# SOC_POWER_CAPS_SOC_VSS.net
KiCad netlist of a schematic drawn in Altium Designer
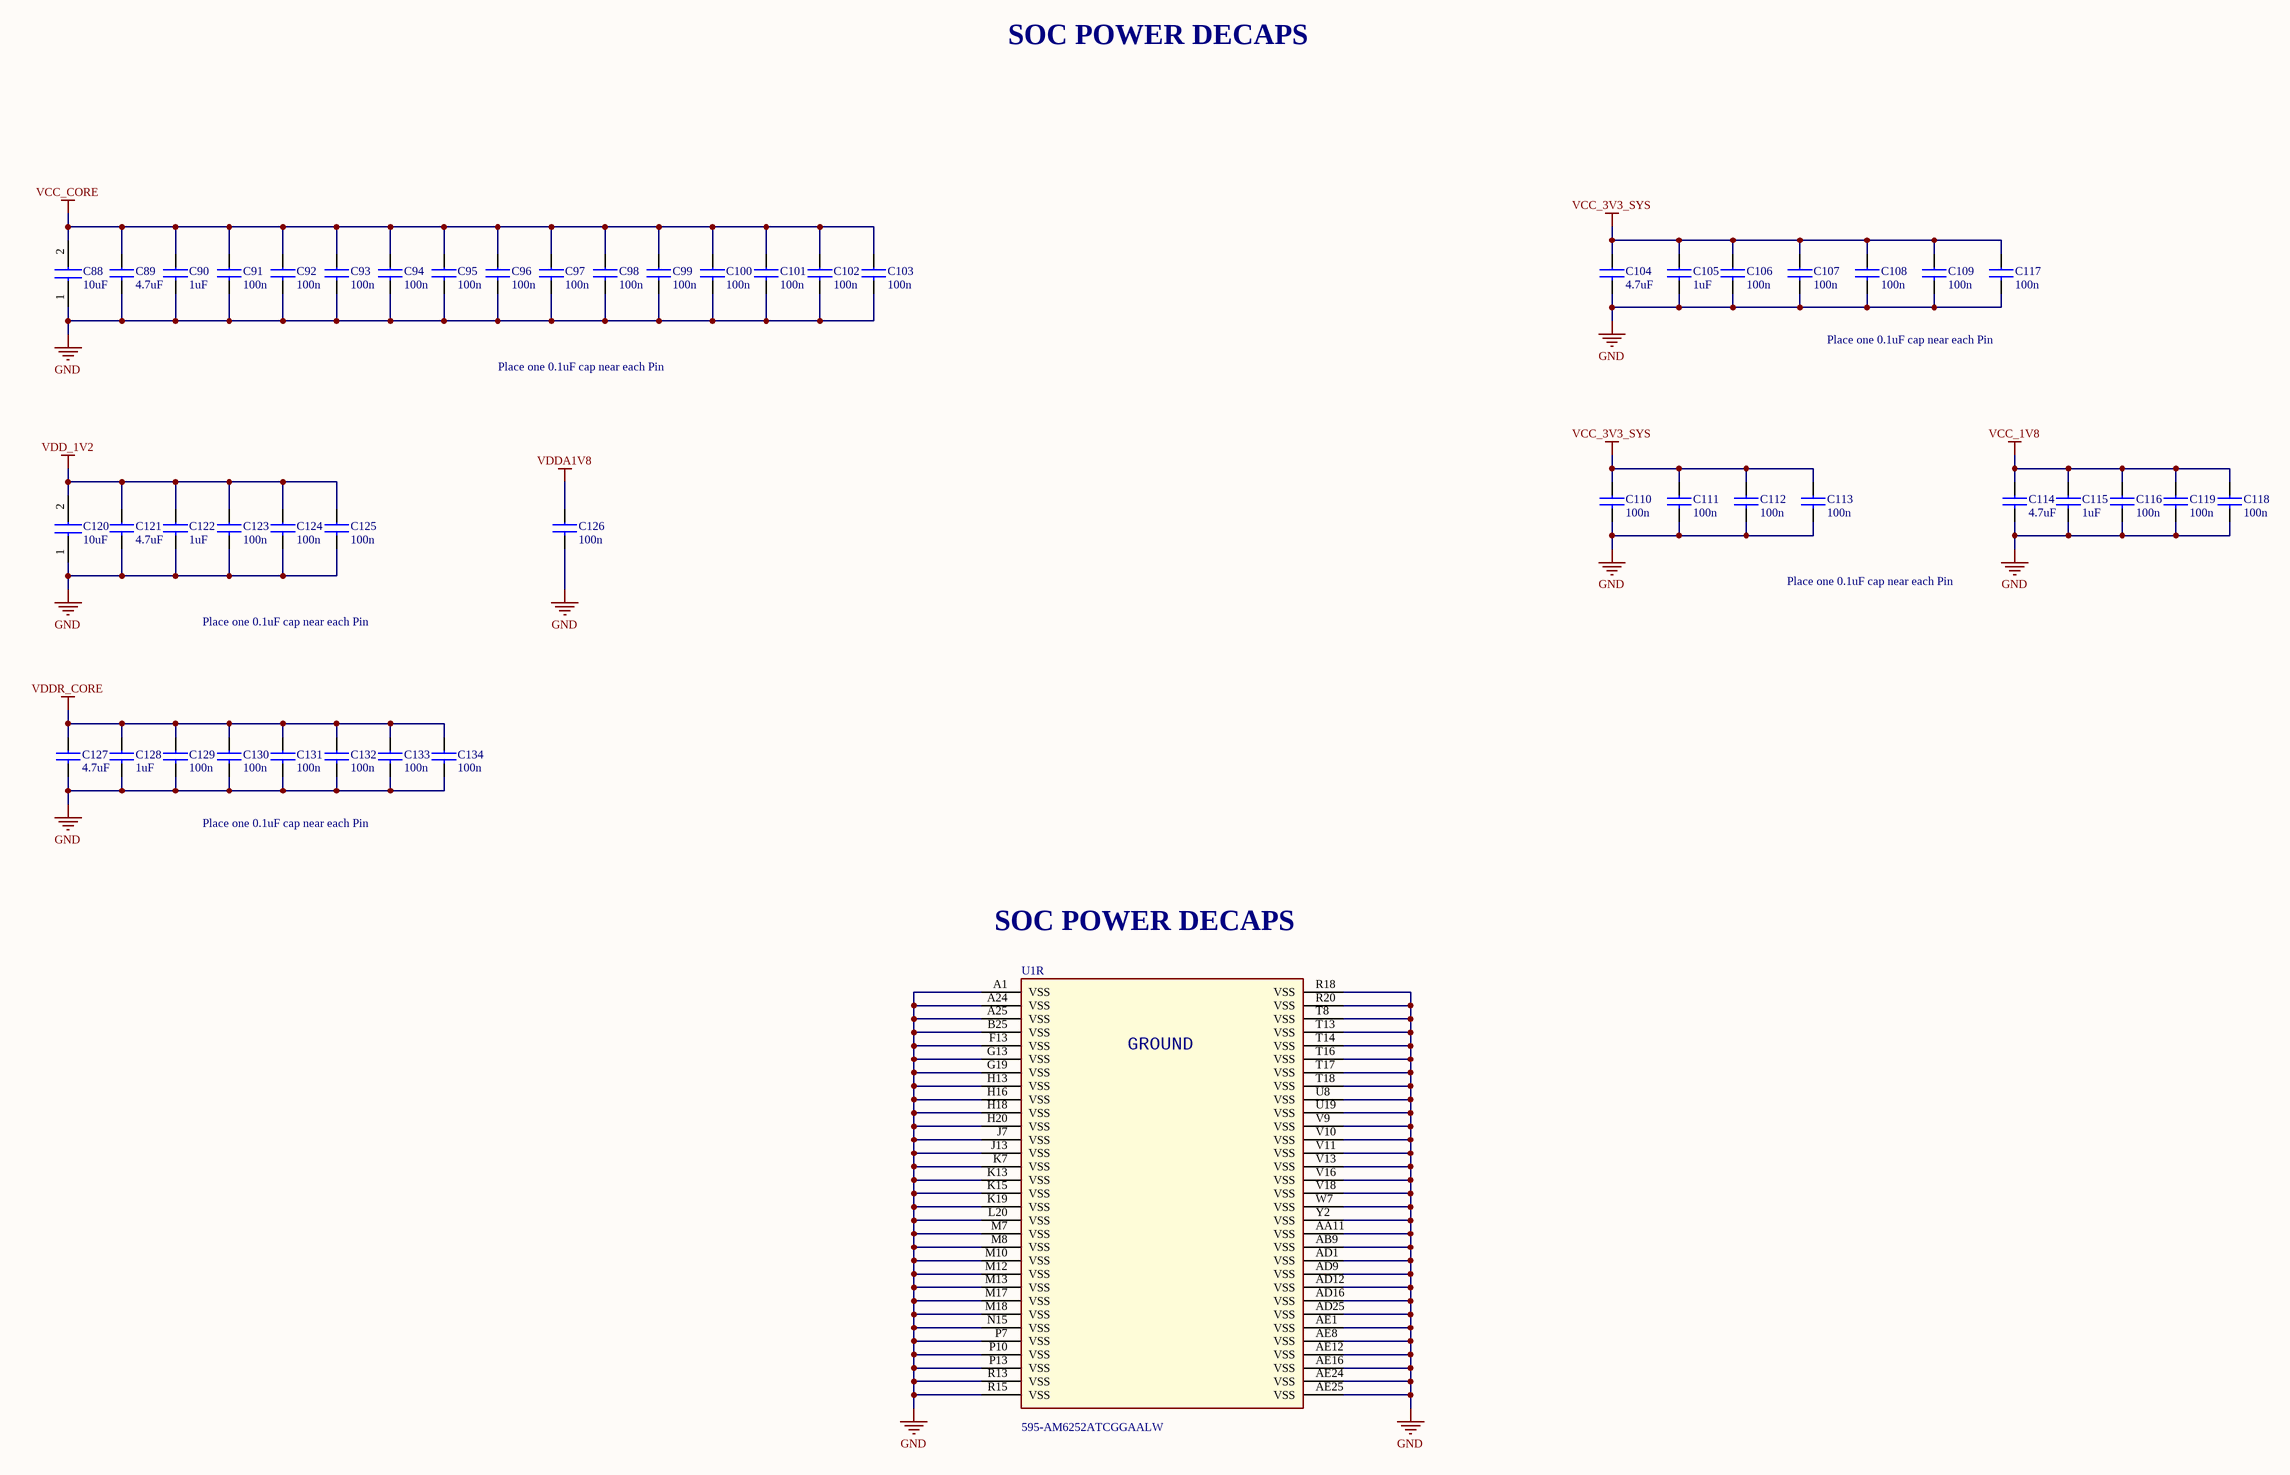
[diagram p0: SOC POWER CAPS & SOC VSS.SchDoc]

(export (version "E")
  (design (tool "Eeschema 10.0.6"))
  (components
    (comp (ref "C88")
      (value "10uF")
      (footprint "C0603")
      (description "10 µF ±20% 6.3V Ceramic Capacitor X5R 0603 (1608 Metric)")
      (fields
        (field (name "MANUFACTURER_PART_NUMBER") "CL10A106MQ8NNNC")
        (field (name "MOUSER PART NUMBER") "187-CL10A106MQ8NNNC")
      )
      (libsource (lib "Schlib AM625") (part "CL10A106MQ8NNNC"))
    )
    (comp (ref "C89")
      (value "4.7uF")
      (footprint "C0201")
      (description "CAP CER 4.7UF 6.3V X5R 0201")
      (fields
        (field (name "MANUFACTURER") "Murata")
        (field (name "MANUFACTURER PART NUMBER") "GRM035R60J475ME15D")
      )
      (libsource (lib "Schlib AM625") (part "GRM035R60J475ME15D"))
    )
    (comp (ref "C90")
      (value "1uF")
      (footprint "C0201")
      (description "CAP CER 1UF 6.3V X5R 0201")
      (fields
        (field (name "MANUFACTURER") "Samsung")
        (field (name "MANUFACTURER PART NUMBER") "CL03A105KQ3CSNC")
      )
      (libsource (lib "Schlib AM625") (part "CL03A105KQ3CSNC"))
    )
    (comp (ref "C91")
      (value "100n")
      (footprint "C0201")
      (description "CAP CER 0.1UF 16V 10% X5R 0201")
      (fields
        (field (name "MANUFACTURER") "TDK Corporation")
        (field (name "MANUFACTURER PART NUMBER") "C0603X5R1C104K030BC")
        (field (name ".CREATOR") "MM")
        (field (name ".CHECKED PCB") "MM")
        (field (name ".CHECKED SCH") "MM")
      )
      (libsource (lib "Schlib AM625") (part "C0603X5R1C104K030BC"))
    )
    (comp (ref "C92")
      (value "100n")
      (footprint "C0201")
      (description "CAP CER 0.1UF 16V 10% X5R 0201")
      (fields
        (field (name "MANUFACTURER") "TDK Corporation")
        (field (name "MANUFACTURER PART NUMBER") "C0603X5R1C104K030BC")
        (field (name ".CREATOR") "MM")
        (field (name ".CHECKED PCB") "MM")
        (field (name ".CHECKED SCH") "MM")
      )
      (libsource (lib "Schlib AM625") (part "C0603X5R1C104K030BC"))
    )
    (comp (ref "C93")
      (value "100n")
      (footprint "C0201")
      (description "CAP CER 0.1UF 16V 10% X5R 0201")
      (fields
        (field (name "MANUFACTURER") "TDK Corporation")
        (field (name "MANUFACTURER PART NUMBER") "C0603X5R1C104K030BC")
        (field (name ".CREATOR") "MM")
        (field (name ".CHECKED PCB") "MM")
        (field (name ".CHECKED SCH") "MM")
      )
      (libsource (lib "Schlib AM625") (part "C0603X5R1C104K030BC"))
    )
    (comp (ref "C94")
      (value "100n")
      (footprint "C0201")
      (description "CAP CER 0.1UF 16V 10% X5R 0201")
      (fields
        (field (name "MANUFACTURER") "TDK Corporation")
        (field (name "MANUFACTURER PART NUMBER") "C0603X5R1C104K030BC")
        (field (name ".CREATOR") "MM")
        (field (name ".CHECKED PCB") "MM")
        (field (name ".CHECKED SCH") "MM")
      )
      (libsource (lib "Schlib AM625") (part "C0603X5R1C104K030BC"))
    )
    (comp (ref "C95")
      (value "100n")
      (footprint "C0201")
      (description "CAP CER 0.1UF 16V 10% X5R 0201")
      (fields
        (field (name "MANUFACTURER") "TDK Corporation")
        (field (name "MANUFACTURER PART NUMBER") "C0603X5R1C104K030BC")
        (field (name ".CREATOR") "MM")
        (field (name ".CHECKED PCB") "MM")
        (field (name ".CHECKED SCH") "MM")
      )
      (libsource (lib "Schlib AM625") (part "C0603X5R1C104K030BC"))
    )
    (comp (ref "C96")
      (value "100n")
      (footprint "C0201")
      (description "CAP CER 0.1UF 16V 10% X5R 0201")
      (fields
        (field (name "MANUFACTURER") "TDK Corporation")
        (field (name "MANUFACTURER PART NUMBER") "C0603X5R1C104K030BC")
        (field (name ".CREATOR") "MM")
        (field (name ".CHECKED PCB") "MM")
        (field (name ".CHECKED SCH") "MM")
      )
      (libsource (lib "Schlib AM625") (part "C0603X5R1C104K030BC"))
    )
    (comp (ref "C97")
      (value "100n")
      (footprint "C0201")
      (description "CAP CER 0.1UF 16V 10% X5R 0201")
      (fields
        (field (name "MANUFACTURER") "TDK Corporation")
        (field (name "MANUFACTURER PART NUMBER") "C0603X5R1C104K030BC")
        (field (name ".CREATOR") "MM")
        (field (name ".CHECKED PCB") "MM")
        (field (name ".CHECKED SCH") "MM")
      )
      (libsource (lib "Schlib AM625") (part "C0603X5R1C104K030BC"))
    )
    (comp (ref "C98")
      (value "100n")
      (footprint "C0201")
      (description "CAP CER 0.1UF 16V 10% X5R 0201")
      (fields
        (field (name "MANUFACTURER") "TDK Corporation")
        (field (name "MANUFACTURER PART NUMBER") "C0603X5R1C104K030BC")
        (field (name ".CREATOR") "MM")
        (field (name ".CHECKED PCB") "MM")
        (field (name ".CHECKED SCH") "MM")
      )
      (libsource (lib "Schlib AM625") (part "C0603X5R1C104K030BC"))
    )
    (comp (ref "C99")
      (value "100n")
      (footprint "C0201")
      (description "CAP CER 0.1UF 16V 10% X5R 0201")
      (fields
        (field (name "MANUFACTURER") "TDK Corporation")
        (field (name "MANUFACTURER PART NUMBER") "C0603X5R1C104K030BC")
        (field (name ".CREATOR") "MM")
        (field (name ".CHECKED PCB") "MM")
        (field (name ".CHECKED SCH") "MM")
      )
      (libsource (lib "Schlib AM625") (part "C0603X5R1C104K030BC"))
    )
    (comp (ref "C100")
      (value "100n")
      (footprint "C0201")
      (description "CAP CER 0.1UF 16V 10% X5R 0201")
      (fields
        (field (name "MANUFACTURER") "TDK Corporation")
        (field (name "MANUFACTURER PART NUMBER") "C0603X5R1C104K030BC")
        (field (name ".CREATOR") "MM")
        (field (name ".CHECKED PCB") "MM")
        (field (name ".CHECKED SCH") "MM")
      )
      (libsource (lib "Schlib AM625") (part "C0603X5R1C104K030BC"))
    )
    (comp (ref "C101")
      (value "100n")
      (footprint "C0201")
      (description "CAP CER 0.1UF 16V 10% X5R 0201")
      (fields
        (field (name "MANUFACTURER") "TDK Corporation")
        (field (name "MANUFACTURER PART NUMBER") "C0603X5R1C104K030BC")
        (field (name ".CREATOR") "MM")
        (field (name ".CHECKED PCB") "MM")
        (field (name ".CHECKED SCH") "MM")
      )
      (libsource (lib "Schlib AM625") (part "C0603X5R1C104K030BC"))
    )
    (comp (ref "C102")
      (value "100n")
      (footprint "C0201")
      (description "CAP CER 0.1UF 16V 10% X5R 0201")
      (fields
        (field (name "MANUFACTURER") "TDK Corporation")
        (field (name "MANUFACTURER PART NUMBER") "C0603X5R1C104K030BC")
        (field (name ".CREATOR") "MM")
        (field (name ".CHECKED PCB") "MM")
        (field (name ".CHECKED SCH") "MM")
      )
      (libsource (lib "Schlib AM625") (part "C0603X5R1C104K030BC"))
    )
    (comp (ref "C103")
      (value "100n")
      (footprint "C0201")
      (description "CAP CER 0.1UF 16V 10% X5R 0201")
      (fields
        (field (name "MANUFACTURER") "TDK Corporation")
        (field (name "MANUFACTURER PART NUMBER") "C0603X5R1C104K030BC")
        (field (name ".CREATOR") "MM")
        (field (name ".CHECKED PCB") "MM")
        (field (name ".CHECKED SCH") "MM")
      )
      (libsource (lib "Schlib AM625") (part "C0603X5R1C104K030BC"))
    )
    (comp (ref "C104")
      (value "4.7uF")
      (footprint "C0201")
      (description "CAP CER 4.7UF 6.3V X5R 0201")
      (fields
        (field (name "MANUFACTURER") "Murata")
        (field (name "MANUFACTURER PART NUMBER") "GRM035R60J475ME15D")
      )
      (libsource (lib "Schlib AM625") (part "GRM035R60J475ME15D"))
    )
    (comp (ref "C105")
      (value "1uF")
      (footprint "C0201")
      (description "CAP CER 1UF 6.3V X5R 0201")
      (fields
        (field (name "MANUFACTURER") "Samsung")
        (field (name "MANUFACTURER PART NUMBER") "CL03A105KQ3CSNC")
      )
      (libsource (lib "Schlib AM625") (part "CL03A105KQ3CSNC"))
    )
    (comp (ref "C106")
      (value "100n")
      (footprint "C0201")
      (description "CAP CER 0.1UF 16V 10% X5R 0201")
      (fields
        (field (name "MANUFACTURER") "TDK Corporation")
        (field (name "MANUFACTURER PART NUMBER") "C0603X5R1C104K030BC")
        (field (name ".CREATOR") "MM")
        (field (name ".CHECKED PCB") "MM")
        (field (name ".CHECKED SCH") "MM")
      )
      (libsource (lib "Schlib AM625") (part "C0603X5R1C104K030BC"))
    )
    (comp (ref "C107")
      (value "100n")
      (footprint "C0201")
      (description "CAP CER 0.1UF 16V 10% X5R 0201")
      (fields
        (field (name "MANUFACTURER") "TDK Corporation")
        (field (name "MANUFACTURER PART NUMBER") "C0603X5R1C104K030BC")
        (field (name ".CREATOR") "MM")
        (field (name ".CHECKED PCB") "MM")
        (field (name ".CHECKED SCH") "MM")
      )
      (libsource (lib "Schlib AM625") (part "C0603X5R1C104K030BC"))
    )
    (comp (ref "C108")
      (value "100n")
      (footprint "C0201")
      (description "CAP CER 0.1UF 16V 10% X5R 0201")
      (fields
        (field (name "MANUFACTURER") "TDK Corporation")
        (field (name "MANUFACTURER PART NUMBER") "C0603X5R1C104K030BC")
        (field (name ".CREATOR") "MM")
        (field (name ".CHECKED PCB") "MM")
        (field (name ".CHECKED SCH") "MM")
      )
      (libsource (lib "Schlib AM625") (part "C0603X5R1C104K030BC"))
    )
    (comp (ref "C109")
      (value "100n")
      (footprint "C0201")
      (description "CAP CER 0.1UF 16V 10% X5R 0201")
      (fields
        (field (name "MANUFACTURER") "TDK Corporation")
        (field (name "MANUFACTURER PART NUMBER") "C0603X5R1C104K030BC")
        (field (name ".CREATOR") "MM")
        (field (name ".CHECKED PCB") "MM")
        (field (name ".CHECKED SCH") "MM")
      )
      (libsource (lib "Schlib AM625") (part "C0603X5R1C104K030BC"))
    )
    (comp (ref "C110")
      (value "100n")
      (footprint "C0201")
      (description "CAP CER 0.1UF 16V 10% X5R 0201")
      (fields
        (field (name "MANUFACTURER") "TDK Corporation")
        (field (name "MANUFACTURER PART NUMBER") "C0603X5R1C104K030BC")
        (field (name ".CREATOR") "MM")
        (field (name ".CHECKED PCB") "MM")
        (field (name ".CHECKED SCH") "MM")
      )
      (libsource (lib "Schlib AM625") (part "C0603X5R1C104K030BC"))
    )
    (comp (ref "C111")
      (value "100n")
      (footprint "C0201")
      (description "CAP CER 0.1UF 16V 10% X5R 0201")
      (fields
        (field (name "MANUFACTURER") "TDK Corporation")
        (field (name "MANUFACTURER PART NUMBER") "C0603X5R1C104K030BC")
        (field (name ".CREATOR") "MM")
        (field (name ".CHECKED PCB") "MM")
        (field (name ".CHECKED SCH") "MM")
      )
      (libsource (lib "Schlib AM625") (part "C0603X5R1C104K030BC"))
    )
    (comp (ref "C112")
      (value "100n")
      (footprint "C0201")
      (description "CAP CER 0.1UF 16V 10% X5R 0201")
      (fields
        (field (name "MANUFACTURER") "TDK Corporation")
        (field (name "MANUFACTURER PART NUMBER") "C0603X5R1C104K030BC")
        (field (name ".CREATOR") "MM")
        (field (name ".CHECKED PCB") "MM")
        (field (name ".CHECKED SCH") "MM")
      )
      (libsource (lib "Schlib AM625") (part "C0603X5R1C104K030BC"))
    )
    (comp (ref "C113")
      (value "100n")
      (footprint "C0201")
      (description "CAP CER 0.1UF 16V 10% X5R 0201")
      (fields
        (field (name "MANUFACTURER") "TDK Corporation")
        (field (name "MANUFACTURER PART NUMBER") "C0603X5R1C104K030BC")
        (field (name ".CREATOR") "MM")
        (field (name ".CHECKED PCB") "MM")
        (field (name ".CHECKED SCH") "MM")
      )
      (libsource (lib "Schlib AM625") (part "C0603X5R1C104K030BC"))
    )
    (comp (ref "C114")
      (value "4.7uF")
      (footprint "C0201")
      (description "CAP CER 4.7UF 6.3V X5R 0201")
      (fields
        (field (name "MANUFACTURER") "Murata")
        (field (name "MANUFACTURER PART NUMBER") "GRM035R60J475ME15D")
      )
      (libsource (lib "Schlib AM625") (part "GRM035R60J475ME15D"))
    )
    (comp (ref "C115")
      (value "1uF")
      (footprint "C0201")
      (description "CAP CER 1UF 6.3V X5R 0201")
      (fields
        (field (name "MANUFACTURER") "Samsung")
        (field (name "MANUFACTURER PART NUMBER") "CL03A105KQ3CSNC")
      )
      (libsource (lib "Schlib AM625") (part "CL03A105KQ3CSNC"))
    )
    (comp (ref "C116")
      (value "100n")
      (footprint "C0201")
      (description "CAP CER 0.1UF 16V 10% X5R 0201")
      (fields
        (field (name "MANUFACTURER") "TDK Corporation")
        (field (name "MANUFACTURER PART NUMBER") "C0603X5R1C104K030BC")
        (field (name ".CREATOR") "MM")
        (field (name ".CHECKED PCB") "MM")
        (field (name ".CHECKED SCH") "MM")
      )
      (libsource (lib "Schlib AM625") (part "C0603X5R1C104K030BC"))
    )
    (comp (ref "C117")
      (value "100n")
      (footprint "C0201")
      (description "CAP CER 0.1UF 16V 10% X5R 0201")
      (fields
        (field (name "MANUFACTURER") "TDK Corporation")
        (field (name "MANUFACTURER PART NUMBER") "C0603X5R1C104K030BC")
        (field (name ".CREATOR") "MM")
        (field (name ".CHECKED PCB") "MM")
        (field (name ".CHECKED SCH") "MM")
      )
      (libsource (lib "Schlib AM625") (part "C0603X5R1C104K030BC"))
    )
    (comp (ref "C118")
      (value "100n")
      (footprint "C0201")
      (description "CAP CER 0.1UF 16V 10% X5R 0201")
      (fields
        (field (name "MANUFACTURER") "TDK Corporation")
        (field (name "MANUFACTURER PART NUMBER") "C0603X5R1C104K030BC")
        (field (name ".CREATOR") "MM")
        (field (name ".CHECKED PCB") "MM")
        (field (name ".CHECKED SCH") "MM")
      )
      (libsource (lib "Schlib AM625") (part "C0603X5R1C104K030BC"))
    )
    (comp (ref "C119")
      (value "100n")
      (footprint "C0201")
      (description "CAP CER 0.1UF 16V 10% X5R 0201")
      (fields
        (field (name "MANUFACTURER") "TDK Corporation")
        (field (name "MANUFACTURER PART NUMBER") "C0603X5R1C104K030BC")
        (field (name ".CREATOR") "MM")
        (field (name ".CHECKED PCB") "MM")
        (field (name ".CHECKED SCH") "MM")
      )
      (libsource (lib "Schlib AM625") (part "C0603X5R1C104K030BC"))
    )
    (comp (ref "C120")
      (value "10uF")
      (footprint "C0603")
      (description "10 µF ±20% 6.3V Ceramic Capacitor X5R 0603 (1608 Metric)")
      (fields
        (field (name "MANUFACTURER_PART_NUMBER") "CL10A106MQ8NNNC")
        (field (name "MOUSER PART NUMBER") "187-CL10A106MQ8NNNC")
      )
      (libsource (lib "Schlib AM625") (part "CL10A106MQ8NNNC"))
    )
    (comp (ref "C121")
      (value "4.7uF")
      (footprint "C0201")
      (description "CAP CER 4.7UF 6.3V X5R 0201")
      (fields
        (field (name "MANUFACTURER") "Murata")
        (field (name "MANUFACTURER PART NUMBER") "GRM035R60J475ME15D")
      )
      (libsource (lib "Schlib AM625") (part "GRM035R60J475ME15D"))
    )
    (comp (ref "C122")
      (value "1uF")
      (footprint "C0201")
      (description "CAP CER 1UF 6.3V X5R 0201")
      (fields
        (field (name "MANUFACTURER") "Samsung")
        (field (name "MANUFACTURER PART NUMBER") "CL03A105KQ3CSNC")
      )
      (libsource (lib "Schlib AM625") (part "CL03A105KQ3CSNC"))
    )
    (comp (ref "C123")
      (value "100n")
      (footprint "C0201")
      (description "CAP CER 0.1UF 16V 10% X5R 0201")
      (fields
        (field (name "MANUFACTURER") "TDK Corporation")
        (field (name "MANUFACTURER PART NUMBER") "C0603X5R1C104K030BC")
        (field (name ".CREATOR") "MM")
        (field (name ".CHECKED PCB") "MM")
        (field (name ".CHECKED SCH") "MM")
      )
      (libsource (lib "Schlib AM625") (part "C0603X5R1C104K030BC"))
    )
    (comp (ref "C124")
      (value "100n")
      (footprint "C0201")
      (description "CAP CER 0.1UF 16V 10% X5R 0201")
      (fields
        (field (name "MANUFACTURER") "TDK Corporation")
        (field (name "MANUFACTURER PART NUMBER") "C0603X5R1C104K030BC")
        (field (name ".CREATOR") "MM")
        (field (name ".CHECKED PCB") "MM")
        (field (name ".CHECKED SCH") "MM")
      )
      (libsource (lib "Schlib AM625") (part "C0603X5R1C104K030BC"))
    )
    (comp (ref "C125")
      (value "100n")
      (footprint "C0201")
      (description "CAP CER 0.1UF 16V 10% X5R 0201")
      (fields
        (field (name "MANUFACTURER") "TDK Corporation")
        (field (name "MANUFACTURER PART NUMBER") "C0603X5R1C104K030BC")
        (field (name ".CREATOR") "MM")
        (field (name ".CHECKED PCB") "MM")
        (field (name ".CHECKED SCH") "MM")
      )
      (libsource (lib "Schlib AM625") (part "C0603X5R1C104K030BC"))
    )
    (comp (ref "C126")
      (value "100n")
      (footprint "C0201")
      (description "CAP CER 0.1UF 16V 10% X5R 0201")
      (fields
        (field (name "MANUFACTURER") "TDK Corporation")
        (field (name "MANUFACTURER PART NUMBER") "C0603X5R1C104K030BC")
        (field (name ".CREATOR") "MM")
        (field (name ".CHECKED PCB") "MM")
        (field (name ".CHECKED SCH") "MM")
      )
      (libsource (lib "Schlib AM625") (part "C0603X5R1C104K030BC"))
    )
    (comp (ref "C127")
      (value "4.7uF")
      (footprint "C0201")
      (description "CAP CER 4.7UF 6.3V X5R 0201")
      (fields
        (field (name "MANUFACTURER") "Murata")
        (field (name "MANUFACTURER PART NUMBER") "GRM035R60J475ME15D")
      )
      (libsource (lib "Schlib AM625") (part "GRM035R60J475ME15D"))
    )
    (comp (ref "C128")
      (value "1uF")
      (footprint "C0201")
      (description "CAP CER 1UF 6.3V X5R 0201")
      (fields
        (field (name "MANUFACTURER") "Samsung")
        (field (name "MANUFACTURER PART NUMBER") "CL03A105KQ3CSNC")
      )
      (libsource (lib "Schlib AM625") (part "CL03A105KQ3CSNC"))
    )
    (comp (ref "C129")
      (value "100n")
      (footprint "C0201")
      (description "CAP CER 0.1UF 16V 10% X5R 0201")
      (fields
        (field (name "MANUFACTURER") "TDK Corporation")
        (field (name "MANUFACTURER PART NUMBER") "C0603X5R1C104K030BC")
        (field (name ".CREATOR") "MM")
        (field (name ".CHECKED PCB") "MM")
        (field (name ".CHECKED SCH") "MM")
      )
      (libsource (lib "Schlib AM625") (part "C0603X5R1C104K030BC"))
    )
    (comp (ref "C130")
      (value "100n")
      (footprint "C0201")
      (description "CAP CER 0.1UF 16V 10% X5R 0201")
      (fields
        (field (name "MANUFACTURER") "TDK Corporation")
        (field (name "MANUFACTURER PART NUMBER") "C0603X5R1C104K030BC")
        (field (name ".CREATOR") "MM")
        (field (name ".CHECKED PCB") "MM")
        (field (name ".CHECKED SCH") "MM")
      )
      (libsource (lib "Schlib AM625") (part "C0603X5R1C104K030BC"))
    )
    (comp (ref "C131")
      (value "100n")
      (footprint "C0201")
      (description "CAP CER 0.1UF 16V 10% X5R 0201")
      (fields
        (field (name "MANUFACTURER") "TDK Corporation")
        (field (name "MANUFACTURER PART NUMBER") "C0603X5R1C104K030BC")
        (field (name ".CREATOR") "MM")
        (field (name ".CHECKED PCB") "MM")
        (field (name ".CHECKED SCH") "MM")
      )
      (libsource (lib "Schlib AM625") (part "C0603X5R1C104K030BC"))
    )
    (comp (ref "C132")
      (value "100n")
      (footprint "C0201")
      (description "CAP CER 0.1UF 16V 10% X5R 0201")
      (fields
        (field (name "MANUFACTURER") "TDK Corporation")
        (field (name "MANUFACTURER PART NUMBER") "C0603X5R1C104K030BC")
        (field (name ".CREATOR") "MM")
        (field (name ".CHECKED PCB") "MM")
        (field (name ".CHECKED SCH") "MM")
      )
      (libsource (lib "Schlib AM625") (part "C0603X5R1C104K030BC"))
    )
    (comp (ref "C133")
      (value "100n")
      (footprint "C0201")
      (description "CAP CER 0.1UF 16V 10% X5R 0201")
      (fields
        (field (name "MANUFACTURER") "TDK Corporation")
        (field (name "MANUFACTURER PART NUMBER") "C0603X5R1C104K030BC")
        (field (name ".CREATOR") "MM")
        (field (name ".CHECKED PCB") "MM")
        (field (name ".CHECKED SCH") "MM")
      )
      (libsource (lib "Schlib AM625") (part "C0603X5R1C104K030BC"))
    )
    (comp (ref "C134")
      (value "100n")
      (footprint "C0201")
      (description "CAP CER 0.1UF 16V 10% X5R 0201")
      (fields
        (field (name "MANUFACTURER") "TDK Corporation")
        (field (name "MANUFACTURER PART NUMBER") "C0603X5R1C104K030BC")
        (field (name ".CREATOR") "MM")
        (field (name ".CHECKED PCB") "MM")
        (field (name ".CHECKED SCH") "MM")
      )
      (libsource (lib "Schlib AM625") (part "C0603X5R1C104K030BC"))
    )
    (comp (ref "U1")
      (value "AM62-EVM_BGA425")
      (footprint "BGA425C50P25X25_1300X1300X89")
      (description "ARM® Cortex®-A53 Microprocessor IC Sitara™ 2 Core, 64-Bit 1.4GHz 425-FCCSP (13x13)")
      (fields
        (field (name "MANUFACTURER") "Texas Instruments")
        (field (name "MANUFACTURER PART NUMBER") "AM6252ATCGGAALW")
        (field (name "SUPPLIER PART NUMBER 1") "595-AM6252ATCGGAALW")
      )
      (libsource (lib "Schlib AM625") (part "AM62-EVM_BGA425"))
    )
  )
  (nets
    (net (code "1") (name "GND") (class "Default")
      (node (ref "C100") (pin "2") (pinfunction "2_2") (pintype "passive"))
      (node (ref "C101") (pin "2") (pinfunction "2_2") (pintype "passive"))
      (node (ref "C102") (pin "2") (pinfunction "2_2") (pintype "passive"))
      (node (ref "C103") (pin "2") (pinfunction "2_2") (pintype "passive"))
      (node (ref "C104") (pin "2") (pinfunction "2_2") (pintype "passive"))
      (node (ref "C105") (pin "2") (pinfunction "2_2") (pintype "passive"))
      (node (ref "C106") (pin "2") (pinfunction "2_2") (pintype "passive"))
      (node (ref "C107") (pin "2") (pinfunction "2_2") (pintype "passive"))
      (node (ref "C108") (pin "2") (pinfunction "2_2") (pintype "passive"))
      (node (ref "C109") (pin "2") (pinfunction "2_2") (pintype "passive"))
      (node (ref "C110") (pin "2") (pinfunction "2_2") (pintype "passive"))
      (node (ref "C111") (pin "2") (pinfunction "2_2") (pintype "passive"))
      (node (ref "C112") (pin "2") (pinfunction "2_2") (pintype "passive"))
      (node (ref "C113") (pin "2") (pinfunction "2_2") (pintype "passive"))
      (node (ref "C114") (pin "2") (pinfunction "2_2") (pintype "passive"))
      (node (ref "C115") (pin "2") (pinfunction "2_2") (pintype "passive"))
      (node (ref "C116") (pin "2") (pinfunction "2_2") (pintype "passive"))
      (node (ref "C117") (pin "2") (pinfunction "2_2") (pintype "passive"))
      (node (ref "C118") (pin "2") (pinfunction "2_2") (pintype "passive"))
      (node (ref "C119") (pin "2") (pinfunction "2_2") (pintype "passive"))
      (node (ref "C120") (pin "1") (pinfunction "1_1") (pintype "passive"))
      (node (ref "C121") (pin "2") (pinfunction "2_2") (pintype "passive"))
      (node (ref "C122") (pin "2") (pinfunction "2_2") (pintype "passive"))
      (node (ref "C123") (pin "2") (pinfunction "2_2") (pintype "passive"))
      (node (ref "C124") (pin "2") (pinfunction "2_2") (pintype "passive"))
      (node (ref "C125") (pin "2") (pinfunction "2_2") (pintype "passive"))
      (node (ref "C126") (pin "2") (pinfunction "2_2") (pintype "passive"))
      (node (ref "C127") (pin "2") (pinfunction "2_2") (pintype "passive"))
      (node (ref "C128") (pin "2") (pinfunction "2_2") (pintype "passive"))
      (node (ref "C129") (pin "2") (pinfunction "2_2") (pintype "passive"))
      (node (ref "C130") (pin "2") (pinfunction "2_2") (pintype "passive"))
      (node (ref "C131") (pin "2") (pinfunction "2_2") (pintype "passive"))
      (node (ref "C132") (pin "2") (pinfunction "2_2") (pintype "passive"))
      (node (ref "C133") (pin "2") (pinfunction "2_2") (pintype "passive"))
      (node (ref "C134") (pin "2") (pinfunction "2_2") (pintype "passive"))
      (node (ref "C88") (pin "1") (pinfunction "1_1") (pintype "passive"))
      (node (ref "C89") (pin "2") (pinfunction "2_2") (pintype "passive"))
      (node (ref "C90") (pin "2") (pinfunction "2_2") (pintype "passive"))
      (node (ref "C91") (pin "2") (pinfunction "2_2") (pintype "passive"))
      (node (ref "C92") (pin "2") (pinfunction "2_2") (pintype "passive"))
      (node (ref "C93") (pin "2") (pinfunction "2_2") (pintype "passive"))
      (node (ref "C94") (pin "2") (pinfunction "2_2") (pintype "passive"))
      (node (ref "C95") (pin "2") (pinfunction "2_2") (pintype "passive"))
      (node (ref "C96") (pin "2") (pinfunction "2_2") (pintype "passive"))
      (node (ref "C97") (pin "2") (pinfunction "2_2") (pintype "passive"))
      (node (ref "C98") (pin "2") (pinfunction "2_2") (pintype "passive"))
      (node (ref "C99") (pin "2") (pinfunction "2_2") (pintype "passive"))
      (node (ref "U1") (pin "A1") (pinfunction "VSS_A1") (pintype "power_in"))
      (node (ref "U1") (pin "A24") (pinfunction "VSS_A24") (pintype "power_in"))
      (node (ref "U1") (pin "A25") (pinfunction "VSS_A25") (pintype "power_in"))
      (node (ref "U1") (pin "AA11") (pinfunction "VSS_AA11") (pintype "power_in"))
      (node (ref "U1") (pin "AB9") (pinfunction "VSS_AB9") (pintype "power_in"))
      (node (ref "U1") (pin "AD1") (pinfunction "VSS_AD1") (pintype "power_in"))
      (node (ref "U1") (pin "AD12") (pinfunction "VSS_AD12") (pintype "power_in"))
      (node (ref "U1") (pin "AD16") (pinfunction "VSS_AD16") (pintype "power_in"))
      (node (ref "U1") (pin "AD25") (pinfunction "VSS_AD25") (pintype "power_in"))
      (node (ref "U1") (pin "AD9") (pinfunction "VSS_AD9") (pintype "power_in"))
      (node (ref "U1") (pin "AE1") (pinfunction "VSS_AE1") (pintype "power_in"))
      (node (ref "U1") (pin "AE12") (pinfunction "VSS_AE12") (pintype "power_in"))
      (node (ref "U1") (pin "AE16") (pinfunction "VSS_AE16") (pintype "power_in"))
      (node (ref "U1") (pin "AE24") (pinfunction "VSS_AE24") (pintype "power_in"))
      (node (ref "U1") (pin "AE25") (pinfunction "VSS_AE25") (pintype "power_in"))
      (node (ref "U1") (pin "AE8") (pinfunction "VSS_AE8") (pintype "power_in"))
      (node (ref "U1") (pin "B25") (pinfunction "VSS_B25") (pintype "power_in"))
      (node (ref "U1") (pin "F13") (pinfunction "VSS_F13") (pintype "power_in"))
      (node (ref "U1") (pin "G13") (pinfunction "VSS_G13") (pintype "power_in"))
      (node (ref "U1") (pin "G19") (pinfunction "VSS_G19") (pintype "power_in"))
      (node (ref "U1") (pin "H13") (pinfunction "VSS_H13") (pintype "power_in"))
      (node (ref "U1") (pin "H16") (pinfunction "VSS_H16") (pintype "power_in"))
      (node (ref "U1") (pin "H18") (pinfunction "VSS_H18") (pintype "power_in"))
      (node (ref "U1") (pin "H20") (pinfunction "VSS_H20") (pintype "power_in"))
      (node (ref "U1") (pin "J13") (pinfunction "VSS_J13") (pintype "power_in"))
      (node (ref "U1") (pin "J7") (pinfunction "VSS_J7") (pintype "power_in"))
      (node (ref "U1") (pin "K13") (pinfunction "VSS_K13") (pintype "power_in"))
      (node (ref "U1") (pin "K15") (pinfunction "VSS_K15") (pintype "power_in"))
      (node (ref "U1") (pin "K19") (pinfunction "VSS_K19") (pintype "power_in"))
      (node (ref "U1") (pin "K7") (pinfunction "VSS_K7") (pintype "power_in"))
      (node (ref "U1") (pin "L20") (pinfunction "VSS_L20") (pintype "power_in"))
      (node (ref "U1") (pin "M10") (pinfunction "VSS_M10") (pintype "power_in"))
      (node (ref "U1") (pin "M12") (pinfunction "VSS_M12") (pintype "power_in"))
      (node (ref "U1") (pin "M13") (pinfunction "VSS_M13") (pintype "power_in"))
      (node (ref "U1") (pin "M17") (pinfunction "VSS_M17") (pintype "power_in"))
      (node (ref "U1") (pin "M18") (pinfunction "VSS_M18") (pintype "power_in"))
      (node (ref "U1") (pin "M7") (pinfunction "VSS_M7") (pintype "power_in"))
      (node (ref "U1") (pin "M8") (pinfunction "VSS_M8") (pintype "power_in"))
      (node (ref "U1") (pin "N15") (pinfunction "VSS_N15") (pintype "power_in"))
      (node (ref "U1") (pin "P10") (pinfunction "VSS_P10") (pintype "power_in"))
      (node (ref "U1") (pin "P13") (pinfunction "VSS_P13") (pintype "power_in"))
      (node (ref "U1") (pin "P7") (pinfunction "VSS_P7") (pintype "power_in"))
      (node (ref "U1") (pin "R13") (pinfunction "VSS_R13") (pintype "power_in"))
      (node (ref "U1") (pin "R15") (pinfunction "VSS_R15") (pintype "power_in"))
      (node (ref "U1") (pin "R18") (pinfunction "VSS_R18") (pintype "power_in"))
      (node (ref "U1") (pin "R20") (pinfunction "VSS_R20") (pintype "power_in"))
      (node (ref "U1") (pin "T13") (pinfunction "VSS_T13") (pintype "power_in"))
      (node (ref "U1") (pin "T14") (pinfunction "VSS_T14") (pintype "power_in"))
      (node (ref "U1") (pin "T16") (pinfunction "VSS_T16") (pintype "power_in"))
      (node (ref "U1") (pin "T17") (pinfunction "VSS_T17") (pintype "power_in"))
      (node (ref "U1") (pin "T18") (pinfunction "VSS_T18") (pintype "power_in"))
      (node (ref "U1") (pin "T8") (pinfunction "VSS_T8") (pintype "power_in"))
      (node (ref "U1") (pin "U19") (pinfunction "VSS_U19") (pintype "power_in"))
      (node (ref "U1") (pin "U8") (pinfunction "VSS_U8") (pintype "power_in"))
      (node (ref "U1") (pin "V10") (pinfunction "VSS_V10") (pintype "power_in"))
      (node (ref "U1") (pin "V11") (pinfunction "VSS_V11") (pintype "power_in"))
      (node (ref "U1") (pin "V13") (pinfunction "VSS_V13") (pintype "power_in"))
      (node (ref "U1") (pin "V16") (pinfunction "VSS_V16") (pintype "power_in"))
      (node (ref "U1") (pin "V18") (pinfunction "VSS_V18") (pintype "power_in"))
      (node (ref "U1") (pin "V9") (pinfunction "VSS_V9") (pintype "power_in"))
      (node (ref "U1") (pin "W7") (pinfunction "VSS_W7") (pintype "power_in"))
      (node (ref "U1") (pin "Y2") (pinfunction "VSS_Y2") (pintype "power_in"))
    )
    (net (code "2") (name "VCC_1V8") (class "Default")
      (node (ref "C114") (pin "1") (pinfunction "1_1") (pintype "passive"))
      (node (ref "C115") (pin "1") (pinfunction "1_1") (pintype "passive"))
      (node (ref "C116") (pin "1") (pinfunction "1_1") (pintype "passive"))
      (node (ref "C118") (pin "1") (pinfunction "1_1") (pintype "passive"))
      (node (ref "C119") (pin "1") (pinfunction "1_1") (pintype "passive"))
    )
    (net (code "3") (name "VCC_3V3_SYS") (class "Default")
      (node (ref "C104") (pin "1") (pinfunction "1_1") (pintype "passive"))
      (node (ref "C105") (pin "1") (pinfunction "1_1") (pintype "passive"))
      (node (ref "C106") (pin "1") (pinfunction "1_1") (pintype "passive"))
      (node (ref "C107") (pin "1") (pinfunction "1_1") (pintype "passive"))
      (node (ref "C108") (pin "1") (pinfunction "1_1") (pintype "passive"))
      (node (ref "C109") (pin "1") (pinfunction "1_1") (pintype "passive"))
      (node (ref "C110") (pin "1") (pinfunction "1_1") (pintype "passive"))
      (node (ref "C111") (pin "1") (pinfunction "1_1") (pintype "passive"))
      (node (ref "C112") (pin "1") (pinfunction "1_1") (pintype "passive"))
      (node (ref "C113") (pin "1") (pinfunction "1_1") (pintype "passive"))
      (node (ref "C117") (pin "1") (pinfunction "1_1") (pintype "passive"))
    )
    (net (code "4") (name "VCC_CORE") (class "Default")
      (node (ref "C100") (pin "1") (pinfunction "1_1") (pintype "passive"))
      (node (ref "C101") (pin "1") (pinfunction "1_1") (pintype "passive"))
      (node (ref "C102") (pin "1") (pinfunction "1_1") (pintype "passive"))
      (node (ref "C103") (pin "1") (pinfunction "1_1") (pintype "passive"))
      (node (ref "C88") (pin "2") (pinfunction "2_2") (pintype "passive"))
      (node (ref "C89") (pin "1") (pinfunction "1_1") (pintype "passive"))
      (node (ref "C90") (pin "1") (pinfunction "1_1") (pintype "passive"))
      (node (ref "C91") (pin "1") (pinfunction "1_1") (pintype "passive"))
      (node (ref "C92") (pin "1") (pinfunction "1_1") (pintype "passive"))
      (node (ref "C93") (pin "1") (pinfunction "1_1") (pintype "passive"))
      (node (ref "C94") (pin "1") (pinfunction "1_1") (pintype "passive"))
      (node (ref "C95") (pin "1") (pinfunction "1_1") (pintype "passive"))
      (node (ref "C96") (pin "1") (pinfunction "1_1") (pintype "passive"))
      (node (ref "C97") (pin "1") (pinfunction "1_1") (pintype "passive"))
      (node (ref "C98") (pin "1") (pinfunction "1_1") (pintype "passive"))
      (node (ref "C99") (pin "1") (pinfunction "1_1") (pintype "passive"))
    )
    (net (code "5") (name "VDDA1V8") (class "Default")
      (node (ref "C126") (pin "1") (pinfunction "1_1") (pintype "passive"))
    )
    (net (code "6") (name "VDDR_CORE") (class "Default")
      (node (ref "C127") (pin "1") (pinfunction "1_1") (pintype "passive"))
      (node (ref "C128") (pin "1") (pinfunction "1_1") (pintype "passive"))
      (node (ref "C129") (pin "1") (pinfunction "1_1") (pintype "passive"))
      (node (ref "C130") (pin "1") (pinfunction "1_1") (pintype "passive"))
      (node (ref "C131") (pin "1") (pinfunction "1_1") (pintype "passive"))
      (node (ref "C132") (pin "1") (pinfunction "1_1") (pintype "passive"))
      (node (ref "C133") (pin "1") (pinfunction "1_1") (pintype "passive"))
      (node (ref "C134") (pin "1") (pinfunction "1_1") (pintype "passive"))
    )
    (net (code "7") (name "VDD_1V2") (class "Default")
      (node (ref "C120") (pin "2") (pinfunction "2_2") (pintype "passive"))
      (node (ref "C121") (pin "1") (pinfunction "1_1") (pintype "passive"))
      (node (ref "C122") (pin "1") (pinfunction "1_1") (pintype "passive"))
      (node (ref "C123") (pin "1") (pinfunction "1_1") (pintype "passive"))
      (node (ref "C124") (pin "1") (pinfunction "1_1") (pintype "passive"))
      (node (ref "C125") (pin "1") (pinfunction "1_1") (pintype "passive"))
    )
  )
)
